# Ilumitunes-IR-String-Controller-v10.net
KiCad netlist of a schematic drawn in EAGLE
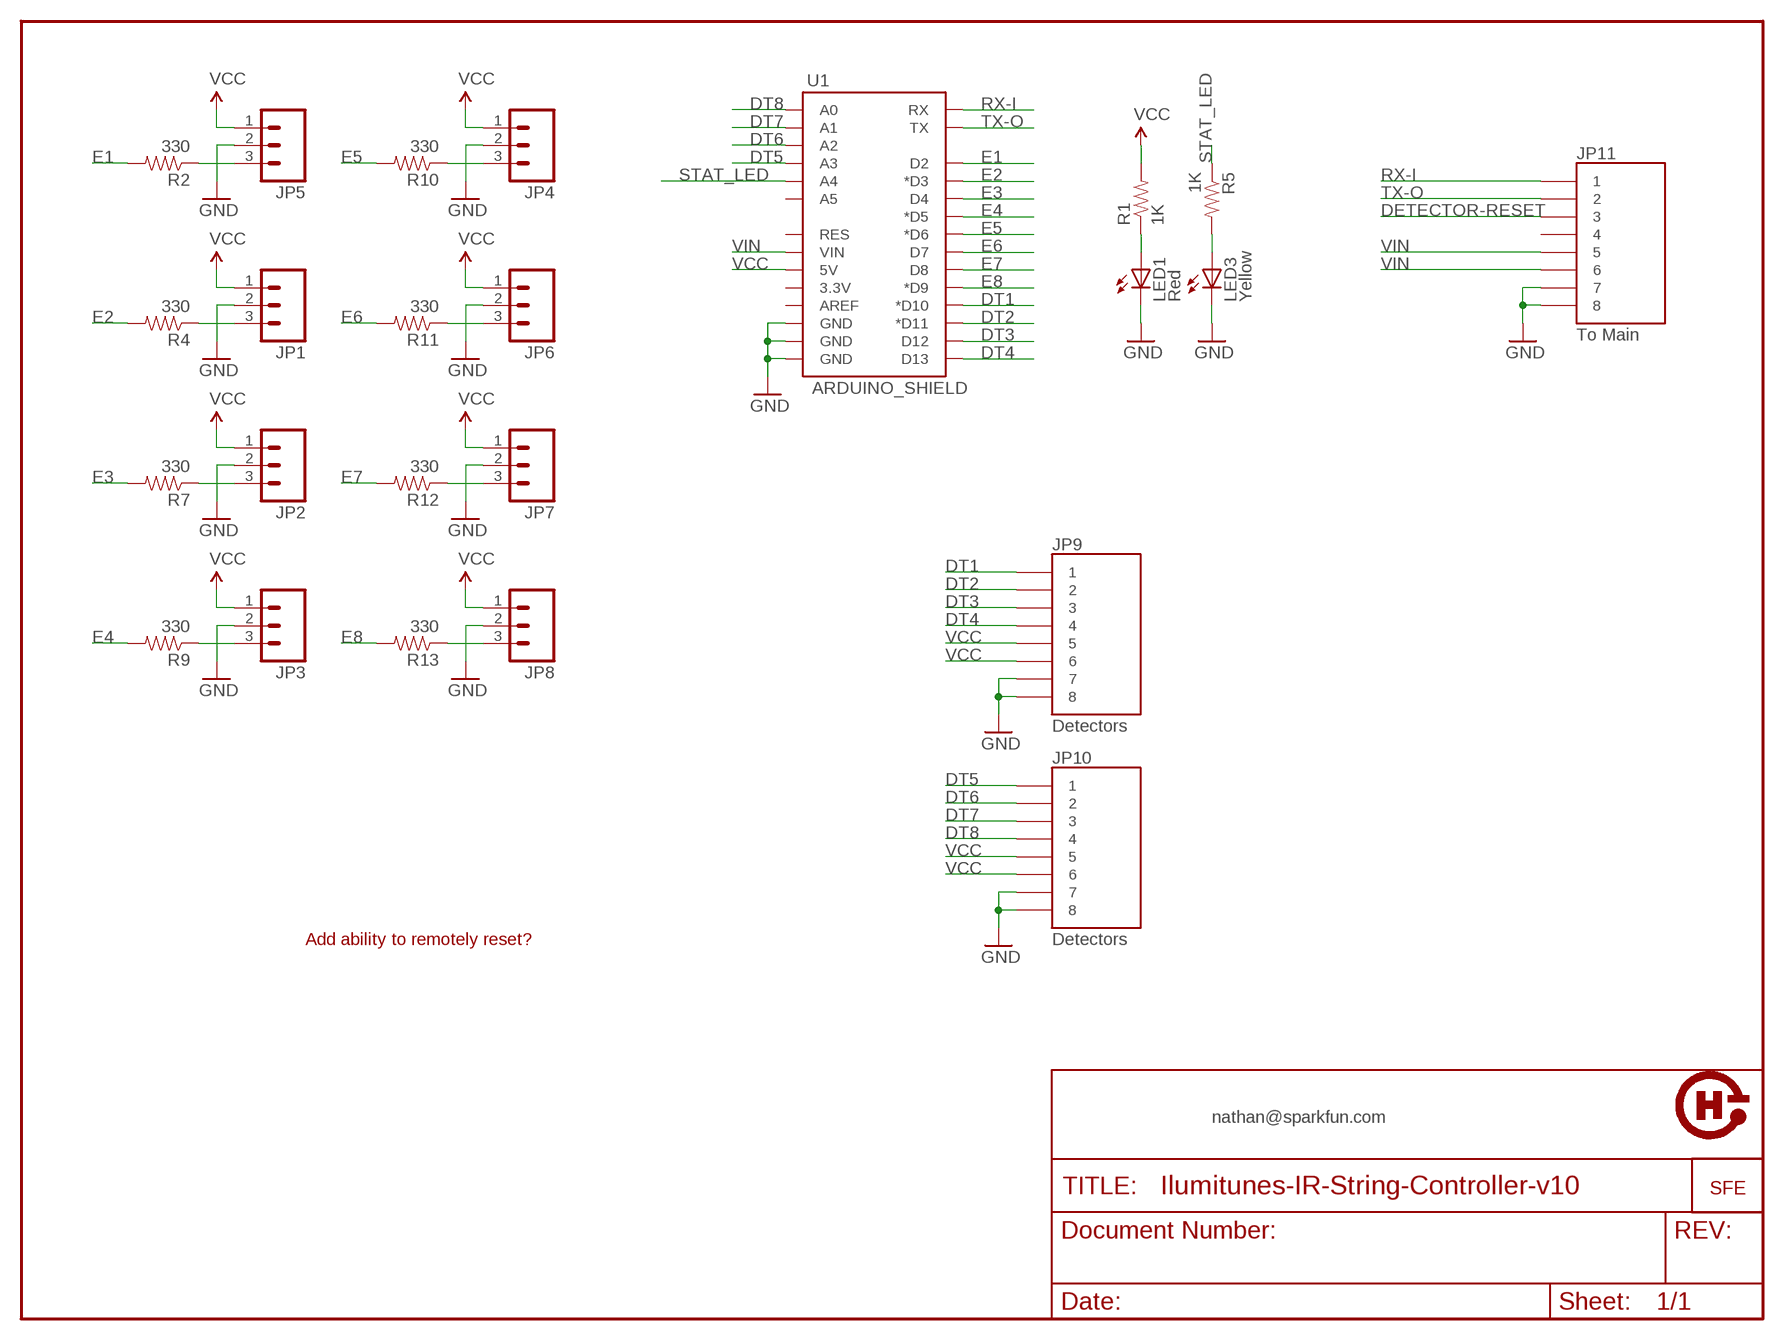
[diagram p0: schematic, sheet 1]

(export (version "E")
  (design (tool "Eeschema 10.0.6"))
  (components
    (comp (ref "JP1")
      (value "M03JST-PTH-VERT")
      (footprint "eagle-import:JST-3-PTH-VERT")
      (libsource (lib "eagle-import") (part "M03JST-PTH-VERT"))
    )
    (comp (ref "JP2")
      (value "M03JST-PTH-VERT")
      (footprint "eagle-import:JST-3-PTH-VERT")
      (libsource (lib "eagle-import") (part "M03JST-PTH-VERT"))
    )
    (comp (ref "JP3")
      (value "M03JST-PTH-VERT")
      (footprint "eagle-import:JST-3-PTH-VERT")
      (libsource (lib "eagle-import") (part "M03JST-PTH-VERT"))
    )
    (comp (ref "JP4")
      (value "M03JST-PTH-VERT")
      (footprint "eagle-import:JST-3-PTH-VERT")
      (libsource (lib "eagle-import") (part "M03JST-PTH-VERT"))
    )
    (comp (ref "JP5")
      (value "M03JST-PTH-VERT")
      (footprint "eagle-import:JST-3-PTH-VERT")
      (libsource (lib "eagle-import") (part "M03JST-PTH-VERT"))
    )
    (comp (ref "JP6")
      (value "M03JST-PTH-VERT")
      (footprint "eagle-import:JST-3-PTH-VERT")
      (libsource (lib "eagle-import") (part "M03JST-PTH-VERT"))
    )
    (comp (ref "JP7")
      (value "M03JST-PTH-VERT")
      (footprint "eagle-import:JST-3-PTH-VERT")
      (libsource (lib "eagle-import") (part "M03JST-PTH-VERT"))
    )
    (comp (ref "JP8")
      (value "M03JST-PTH-VERT")
      (footprint "eagle-import:JST-3-PTH-VERT")
      (libsource (lib "eagle-import") (part "M03JST-PTH-VERT"))
    )
    (comp (ref "JP9")
      (value "Detectors")
      (footprint "eagle-import:RJ45-8")
      (libsource (lib "eagle-import") (part "RJ45-8PTH"))
    )
    (comp (ref "JP10")
      (value "Detectors")
      (footprint "eagle-import:RJ45-8")
      (libsource (lib "eagle-import") (part "RJ45-8PTH"))
    )
    (comp (ref "JP11")
      (value "To Main")
      (footprint "eagle-import:RJ45-8")
      (libsource (lib "eagle-import") (part "RJ45-8PTH"))
    )
    (comp (ref "LED1")
      (value "Red")
      (footprint "eagle-import:LED5MM")
      (libsource (lib "eagle-import") (part "LED5MM"))
    )
    (comp (ref "LED3")
      (value "Yellow")
      (footprint "eagle-import:LED5MM")
      (libsource (lib "eagle-import") (part "LED5MM"))
    )
    (comp (ref "R1")
      (value "1K")
      (footprint "eagle-import:AXIAL-0.3")
      (libsource (lib "eagle-import") (part "RESISTORAXIAL-0.3"))
    )
    (comp (ref "R2")
      (value "330")
      (footprint "eagle-import:AXIAL-0.3")
      (libsource (lib "eagle-import") (part "RESISTORAXIAL-0.3"))
    )
    (comp (ref "R4")
      (value "330")
      (footprint "eagle-import:AXIAL-0.3")
      (libsource (lib "eagle-import") (part "RESISTORAXIAL-0.3"))
    )
    (comp (ref "R5")
      (value "1K")
      (footprint "eagle-import:AXIAL-0.3")
      (libsource (lib "eagle-import") (part "RESISTORAXIAL-0.3"))
    )
    (comp (ref "R7")
      (value "330")
      (footprint "eagle-import:AXIAL-0.3")
      (libsource (lib "eagle-import") (part "RESISTORAXIAL-0.3"))
    )
    (comp (ref "R9")
      (value "330")
      (footprint "eagle-import:AXIAL-0.3")
      (libsource (lib "eagle-import") (part "RESISTORAXIAL-0.3"))
    )
    (comp (ref "R10")
      (value "330")
      (footprint "eagle-import:AXIAL-0.3")
      (libsource (lib "eagle-import") (part "RESISTORAXIAL-0.3"))
    )
    (comp (ref "R11")
      (value "330")
      (footprint "eagle-import:AXIAL-0.3")
      (libsource (lib "eagle-import") (part "RESISTORAXIAL-0.3"))
    )
    (comp (ref "R12")
      (value "330")
      (footprint "eagle-import:AXIAL-0.3")
      (libsource (lib "eagle-import") (part "RESISTORAXIAL-0.3"))
    )
    (comp (ref "R13")
      (value "330")
      (footprint "eagle-import:AXIAL-0.3")
      (libsource (lib "eagle-import") (part "RESISTORAXIAL-0.3"))
    )
    (comp (ref "U$1")
      (value "LOGO-SFENEW")
      (footprint "eagle-import:SFE-NEW-WEBLOGO")
      (libsource (lib "eagle-import") (part "LOGO-SFENEW"))
    )
    (comp (ref "U$2")
      (value "OSHW-LOGO")
      (footprint "eagle-import:OSHW-LOGO")
      (libsource (lib "eagle-import") (part "OSHW-LOGO"))
    )
    (comp (ref "U1")
      (value "ARDUINO_SHIELD")
      (footprint "eagle-import:DUEMILANOVE_SHIELD")
      (libsource (lib "eagle-import") (part "ARDUINO_SHIELDLABEL"))
    )
  )
  (nets
    (net (code "1") (name "/DETECTOR-RESET") (class "Default")
      (node (ref "JP11") (pin "3") (pinfunction "3_3") (pintype "bidirectional"))
    )
    (net (code "2") (name "/DT1") (class "Default")
      (node (ref "JP9") (pin "1") (pinfunction "1_1") (pintype "bidirectional"))
      (node (ref "U1") (pin "D10") (pinfunction "*D10_D10") (pintype "bidirectional"))
    )
    (net (code "3") (name "/DT2") (class "Default")
      (node (ref "JP9") (pin "2") (pinfunction "2_2") (pintype "bidirectional"))
      (node (ref "U1") (pin "D11") (pinfunction "*D11_D11") (pintype "bidirectional"))
    )
    (net (code "4") (name "/DT3") (class "Default")
      (node (ref "JP9") (pin "3") (pinfunction "3_3") (pintype "bidirectional"))
      (node (ref "U1") (pin "D12") (pinfunction "D12_D12") (pintype "bidirectional"))
    )
    (net (code "5") (name "/DT4") (class "Default")
      (node (ref "JP9") (pin "4") (pinfunction "4_4") (pintype "bidirectional"))
      (node (ref "U1") (pin "D13") (pinfunction "D13_D13") (pintype "bidirectional"))
    )
    (net (code "6") (name "/DT5") (class "Default")
      (node (ref "JP10") (pin "1") (pinfunction "1_1") (pintype "bidirectional"))
      (node (ref "U1") (pin "A3") (pinfunction "A3_A3") (pintype "bidirectional"))
    )
    (net (code "7") (name "/DT6") (class "Default")
      (node (ref "JP10") (pin "2") (pinfunction "2_2") (pintype "bidirectional"))
      (node (ref "U1") (pin "A2") (pinfunction "A2_A2") (pintype "bidirectional"))
    )
    (net (code "8") (name "/DT7") (class "Default")
      (node (ref "JP10") (pin "3") (pinfunction "3_3") (pintype "bidirectional"))
      (node (ref "U1") (pin "A1") (pinfunction "A1_A1") (pintype "bidirectional"))
    )
    (net (code "9") (name "/DT8") (class "Default")
      (node (ref "JP10") (pin "4") (pinfunction "4_4") (pintype "bidirectional"))
      (node (ref "U1") (pin "A0") (pinfunction "A0_A0") (pintype "bidirectional"))
    )
    (net (code "10") (name "/E1") (class "Default")
      (node (ref "R2") (pin "P$2") (pinfunction "2_P$2") (pintype "passive"))
      (node (ref "U1") (pin "D2") (pinfunction "D2_D2") (pintype "bidirectional"))
    )
    (net (code "11") (name "/E2") (class "Default")
      (node (ref "R4") (pin "P$2") (pinfunction "2_P$2") (pintype "passive"))
      (node (ref "U1") (pin "D3") (pinfunction "*D3_D3") (pintype "bidirectional"))
    )
    (net (code "12") (name "/E3") (class "Default")
      (node (ref "R7") (pin "P$2") (pinfunction "2_P$2") (pintype "passive"))
      (node (ref "U1") (pin "D4") (pinfunction "D4_D4") (pintype "bidirectional"))
    )
    (net (code "13") (name "/E4") (class "Default")
      (node (ref "R9") (pin "P$2") (pinfunction "2_P$2") (pintype "passive"))
      (node (ref "U1") (pin "D5") (pinfunction "*D5_D5") (pintype "bidirectional"))
    )
    (net (code "14") (name "/E5") (class "Default")
      (node (ref "R10") (pin "P$2") (pinfunction "2_P$2") (pintype "passive"))
      (node (ref "U1") (pin "D6") (pinfunction "*D6_D6") (pintype "bidirectional"))
    )
    (net (code "15") (name "/E6") (class "Default")
      (node (ref "R11") (pin "P$2") (pinfunction "2_P$2") (pintype "passive"))
      (node (ref "U1") (pin "D7") (pinfunction "D7_D7") (pintype "bidirectional"))
    )
    (net (code "16") (name "/E7") (class "Default")
      (node (ref "R12") (pin "P$2") (pinfunction "2_P$2") (pintype "passive"))
      (node (ref "U1") (pin "D8") (pinfunction "D8_D8") (pintype "bidirectional"))
    )
    (net (code "17") (name "/E8") (class "Default")
      (node (ref "R13") (pin "P$2") (pinfunction "2_P$2") (pintype "passive"))
      (node (ref "U1") (pin "D9") (pinfunction "*D9_D9") (pintype "bidirectional"))
    )
    (net (code "18") (name "/RX-I") (class "Default")
      (node (ref "JP11") (pin "1") (pinfunction "1_1") (pintype "bidirectional"))
      (node (ref "U1") (pin "RX") (pinfunction "RX_RX") (pintype "bidirectional"))
    )
    (net (code "19") (name "/STAT_LED") (class "Default")
      (node (ref "R5") (pin "P$1") (pinfunction "1_P$1") (pintype "passive"))
      (node (ref "U1") (pin "A4") (pinfunction "A4_A4") (pintype "bidirectional"))
    )
    (net (code "20") (name "/TX-O") (class "Default")
      (node (ref "JP11") (pin "2") (pinfunction "2_2") (pintype "bidirectional"))
      (node (ref "U1") (pin "TX") (pinfunction "TX_TX") (pintype "bidirectional"))
    )
    (net (code "21") (name "/VIN") (class "Default")
      (node (ref "JP11") (pin "5") (pinfunction "5_5") (pintype "bidirectional"))
      (node (ref "JP11") (pin "6") (pinfunction "6_6") (pintype "bidirectional"))
      (node (ref "U1") (pin "VIN") (pinfunction "VIN_VIN") (pintype "bidirectional"))
    )
    (net (code "22") (name "GND") (class "Default")
      (node (ref "JP1") (pin "2") (pinfunction "2_2") (pintype "passive"))
      (node (ref "JP10") (pin "7") (pinfunction "7_7") (pintype "bidirectional"))
      (node (ref "JP10") (pin "8") (pinfunction "8_8") (pintype "bidirectional"))
      (node (ref "JP11") (pin "7") (pinfunction "7_7") (pintype "bidirectional"))
      (node (ref "JP11") (pin "8") (pinfunction "8_8") (pintype "bidirectional"))
      (node (ref "JP2") (pin "2") (pinfunction "2_2") (pintype "passive"))
      (node (ref "JP3") (pin "2") (pinfunction "2_2") (pintype "passive"))
      (node (ref "JP4") (pin "2") (pinfunction "2_2") (pintype "passive"))
      (node (ref "JP5") (pin "2") (pinfunction "2_2") (pintype "passive"))
      (node (ref "JP6") (pin "2") (pinfunction "2_2") (pintype "passive"))
      (node (ref "JP7") (pin "2") (pinfunction "2_2") (pintype "passive"))
      (node (ref "JP8") (pin "2") (pinfunction "2_2") (pintype "passive"))
      (node (ref "JP9") (pin "7") (pinfunction "7_7") (pintype "bidirectional"))
      (node (ref "JP9") (pin "8") (pinfunction "8_8") (pintype "bidirectional"))
      (node (ref "LED1") (pin "K") (pinfunction "C_K") (pintype "passive"))
      (node (ref "LED3") (pin "K") (pinfunction "C_K") (pintype "passive"))
      (node (ref "U1") (pin "GND@0") (pinfunction "GND_GND@0") (pintype "bidirectional"))
      (node (ref "U1") (pin "GND@1") (pinfunction "GND_GND@1") (pintype "bidirectional"))
      (node (ref "U1") (pin "GND@2") (pinfunction "GND_GND@2") (pintype "bidirectional"))
    )
    (net (code "23") (name "Net-(R1-1)") (class "Default")
      (node (ref "LED1") (pin "A") (pinfunction "A_A") (pintype "passive"))
      (node (ref "R1") (pin "P$1") (pinfunction "1_P$1") (pintype "passive"))
    )
    (net (code "24") (name "Net-(R2-1)") (class "Default")
      (node (ref "JP5") (pin "3") (pinfunction "3_3") (pintype "passive"))
      (node (ref "R2") (pin "P$1") (pinfunction "1_P$1") (pintype "passive"))
    )
    (net (code "25") (name "Net-(R4-1)") (class "Default")
      (node (ref "JP1") (pin "3") (pinfunction "3_3") (pintype "passive"))
      (node (ref "R4") (pin "P$1") (pinfunction "1_P$1") (pintype "passive"))
    )
    (net (code "26") (name "Net-(R5-2)") (class "Default")
      (node (ref "LED3") (pin "A") (pinfunction "A_A") (pintype "passive"))
      (node (ref "R5") (pin "P$2") (pinfunction "2_P$2") (pintype "passive"))
    )
    (net (code "27") (name "Net-(R7-1)") (class "Default")
      (node (ref "JP2") (pin "3") (pinfunction "3_3") (pintype "passive"))
      (node (ref "R7") (pin "P$1") (pinfunction "1_P$1") (pintype "passive"))
    )
    (net (code "28") (name "Net-(R9-1)") (class "Default")
      (node (ref "JP3") (pin "3") (pinfunction "3_3") (pintype "passive"))
      (node (ref "R9") (pin "P$1") (pinfunction "1_P$1") (pintype "passive"))
    )
    (net (code "29") (name "Net-(R10-1)") (class "Default")
      (node (ref "JP4") (pin "3") (pinfunction "3_3") (pintype "passive"))
      (node (ref "R10") (pin "P$1") (pinfunction "1_P$1") (pintype "passive"))
    )
    (net (code "30") (name "Net-(R11-1)") (class "Default")
      (node (ref "JP6") (pin "3") (pinfunction "3_3") (pintype "passive"))
      (node (ref "R11") (pin "P$1") (pinfunction "1_P$1") (pintype "passive"))
    )
    (net (code "31") (name "Net-(R12-1)") (class "Default")
      (node (ref "JP7") (pin "3") (pinfunction "3_3") (pintype "passive"))
      (node (ref "R12") (pin "P$1") (pinfunction "1_P$1") (pintype "passive"))
    )
    (net (code "32") (name "Net-(R13-1)") (class "Default")
      (node (ref "JP8") (pin "3") (pinfunction "3_3") (pintype "passive"))
      (node (ref "R13") (pin "P$1") (pinfunction "1_P$1") (pintype "passive"))
    )
    (net (code "33") (name "VCC") (class "Default")
      (node (ref "JP1") (pin "1") (pinfunction "1_1") (pintype "passive"))
      (node (ref "JP10") (pin "5") (pinfunction "5_5") (pintype "bidirectional"))
      (node (ref "JP10") (pin "6") (pinfunction "6_6") (pintype "bidirectional"))
      (node (ref "JP2") (pin "1") (pinfunction "1_1") (pintype "passive"))
      (node (ref "JP3") (pin "1") (pinfunction "1_1") (pintype "passive"))
      (node (ref "JP4") (pin "1") (pinfunction "1_1") (pintype "passive"))
      (node (ref "JP5") (pin "1") (pinfunction "1_1") (pintype "passive"))
      (node (ref "JP6") (pin "1") (pinfunction "1_1") (pintype "passive"))
      (node (ref "JP7") (pin "1") (pinfunction "1_1") (pintype "passive"))
      (node (ref "JP8") (pin "1") (pinfunction "1_1") (pintype "passive"))
      (node (ref "JP9") (pin "5") (pinfunction "5_5") (pintype "bidirectional"))
      (node (ref "JP9") (pin "6") (pinfunction "6_6") (pintype "bidirectional"))
      (node (ref "R1") (pin "P$2") (pinfunction "2_P$2") (pintype "passive"))
      (node (ref "U1") (pin "5V") (pinfunction "5V_5V") (pintype "bidirectional"))
    )
    (net (code "34") (name "unconnected-(JP11-Pad4)") (class "Default")
      (node (ref "JP11") (pin "4") (pinfunction "4_4") (pintype "bidirectional"))
    )
    (net (code "35") (name "unconnected-(U1-Pad3.3V)") (class "Default")
      (node (ref "U1") (pin "3.3V") (pinfunction "3.3V_3.3V") (pintype "bidirectional"))
    )
    (net (code "36") (name "unconnected-(U1-PadA5)") (class "Default")
      (node (ref "U1") (pin "A5") (pinfunction "A5_A5") (pintype "bidirectional"))
    )
    (net (code "37") (name "unconnected-(U1-PadAREF)") (class "Default")
      (node (ref "U1") (pin "AREF") (pinfunction "AREF_AREF") (pintype "bidirectional"))
    )
    (net (code "38") (name "unconnected-(U1-PadRES)") (class "Default")
      (node (ref "U1") (pin "RES") (pinfunction "RES_RES") (pintype "bidirectional"))
    )
  )
)
